# SCH_Hacker_Card_2023-11-26.net
KiCad netlist of a schematic drawn in EasyEDA
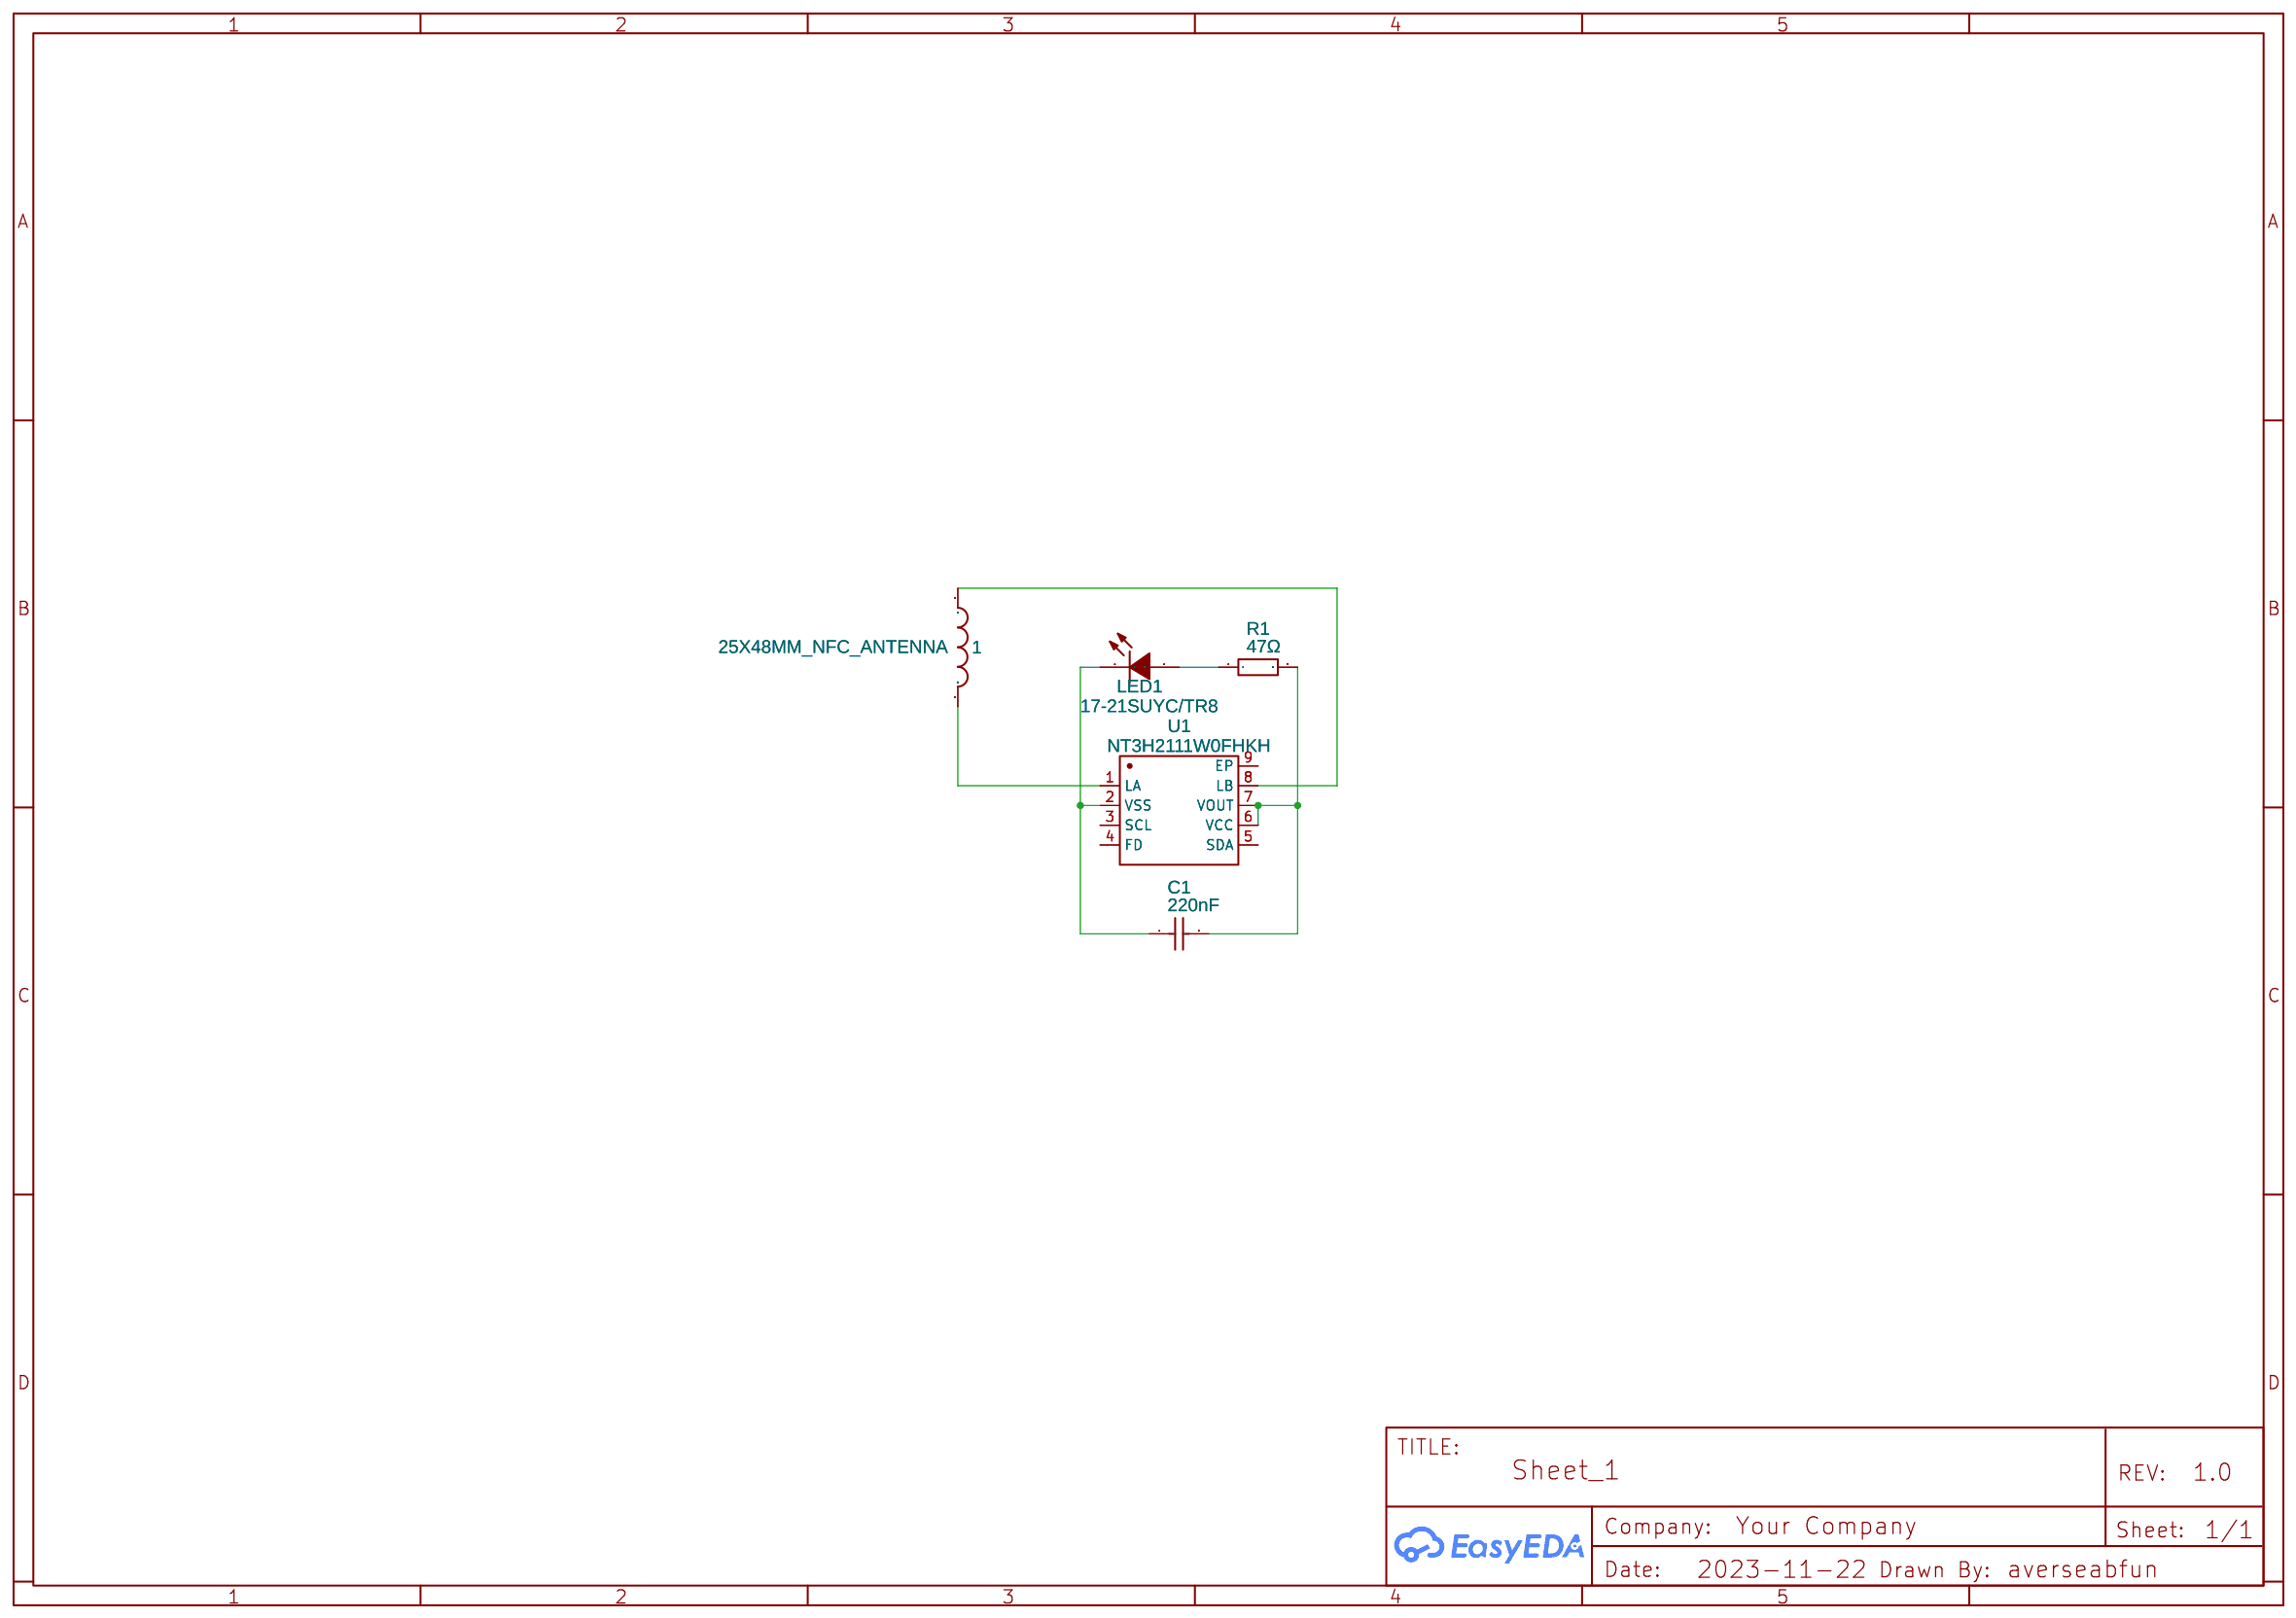
[diagram p0: schematic sheet]

(export (version "E")
  (design (tool "Eeschema 10.0.6"))
  (components
    (comp (ref "1") (value "25X48MM_NFC_ANTENNA") (libsource (lib "") (part "25X48MM_NFC_ANTENNA")))
    (comp (ref "C1")
      (value "220nF")
      (fields
        (field (name "Manufacturer Part") "CL10B224KA8NNNC")
        (field (name "Manufacturer") "SAMSUNG(三星)")
      )
      (libsource (lib "") (part "CL10B224KA8NNNC"))
    )
    (comp (ref "LED1")
      (value "17-21SUYC/TR8")
      (fields (field (name "Manufacturer Part") "KT-0805黄灯") (field (name "Manufacturer") "KENTO"))
      (libsource (lib "") (part "17-21SUYC/TR8"))
    )
    (comp (ref "R1")
      (value "47Ω")
      (fields
        (field (name "Manufacturer Part") "0603WAF470JT5E")
        (field (name "Manufacturer") "UNI-ROYAL(厚声)")
      )
      (libsource (lib "") (part "0603WAF470JT5E"))
    )
    (comp (ref "U1")
      (value "NT3H2111W0FHKH")
      (fields (field (name "Manufacturer") "NXP(恩智浦)"))
      (libsource (lib "") (part "NT3H2111W0FHKH"))
    )
  )
  (nets
    (net (code "1") (name "Net-(LED1-+)") (class "Default")
      (node (ref "LED1") (pin "1") (pinfunction "+_1") (pintype "unspecified"))
      (node (ref "R1") (pin "1") (pinfunction "1_1") (pintype "input"))
    )
    (net (code "2") (name "Net-(LED1--)") (class "Default")
      (node (ref "C1") (pin "1") (pinfunction "1_1") (pintype "input"))
      (node (ref "LED1") (pin "2") (pinfunction "-_2") (pintype "unspecified"))
      (node (ref "U1") (pin "2") (pinfunction "VSS_2") (pintype "unspecified"))
    )
    (net (code "3") (name "Net-(U1-LA)") (class "Default")
      (node (ref "1") (pin "P$2") (pinfunction "P$2_P$2") (pintype "bidirectional"))
      (node (ref "U1") (pin "1") (pinfunction "LA_1") (pintype "unspecified"))
    )
    (net (code "4") (name "Net-(U1-LB)") (class "Default")
      (node (ref "1") (pin "P$1") (pinfunction "P$1_P$1") (pintype "bidirectional"))
      (node (ref "U1") (pin "8") (pinfunction "LB_8") (pintype "unspecified"))
    )
    (net (code "5") (name "Net-(U1-VCC)") (class "Default")
      (node (ref "C1") (pin "2") (pinfunction "2_2") (pintype "input"))
      (node (ref "R1") (pin "2") (pinfunction "2_2") (pintype "input"))
      (node (ref "U1") (pin "6") (pinfunction "VCC_6") (pintype "unspecified"))
      (node (ref "U1") (pin "7") (pinfunction "VOUT_7") (pintype "unspecified"))
    )
    (net (code "6") (name "unconnected-(U1-EP-Pad9)") (class "Default")
      (node (ref "U1") (pin "9") (pinfunction "EP_9") (pintype "unspecified"))
    )
    (net (code "7") (name "unconnected-(U1-FD-Pad4)") (class "Default")
      (node (ref "U1") (pin "4") (pinfunction "FD_4") (pintype "unspecified"))
    )
    (net (code "8") (name "unconnected-(U1-SCL-Pad3)") (class "Default")
      (node (ref "U1") (pin "3") (pinfunction "SCL_3") (pintype "unspecified"))
    )
    (net (code "9") (name "unconnected-(U1-SDA-Pad5)") (class "Default")
      (node (ref "U1") (pin "5") (pinfunction "SDA_5") (pintype "unspecified"))
    )
  )
)
